# PreAmplifierBuffer.net
KiCad netlist of a schematic drawn in Altium Designer
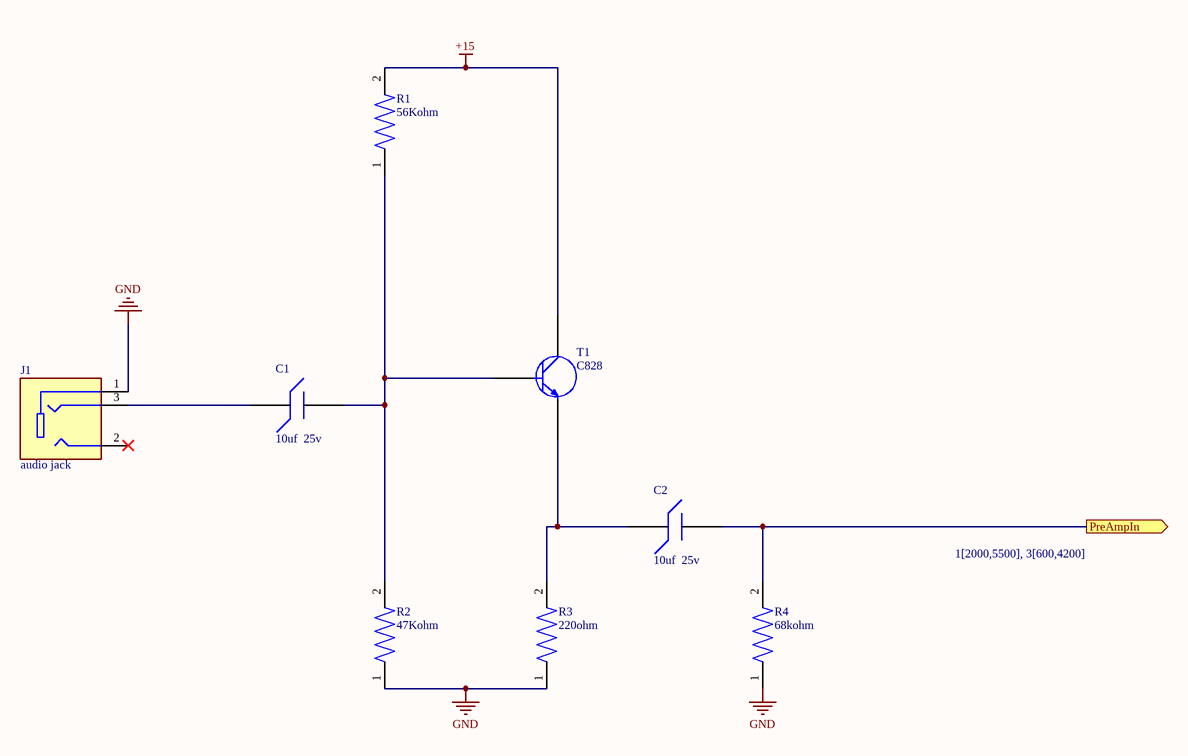
[diagram p0: PreAmplifierBuffer.SchDoc]

(export (version "E")
  (design (tool "Eeschema 10.0.6"))
  (components
    (comp (ref "C1")
      (value "10uf  25v")
      (footprint "Capasitor")
      (fields
        (field (name "MANUFACTURER") "Rubycon")
        (field (name "MANUFACTURER PART NUMBER") "25ZLG10MEFC4X7")
      )
      (libsource (lib "AudioAmplifierBasic") (part "25ZLG10MEFC4X7"))
    )
    (comp (ref "C2")
      (value "10uf  25v")
      (footprint "Capasitor")
      (fields
        (field (name "MANUFACTURER") "Rubycon")
        (field (name "MANUFACTURER PART NUMBER") "25ZLG10MEFC4X7")
      )
      (libsource (lib "AudioAmplifierBasic") (part "25ZLG10MEFC4X7"))
    )
    (comp (ref "J1")
      (value "audio jack")
      (footprint "AudiJack")
      (description "3 Pole(s), Solder Terminal, Jack")
      (fields (field (name "MANUFACTURER") "Same Sky") (field (name "MANUFACTURER PART NUMBER") "SJ1-3523N"))
      (libsource (lib "AudioAmplifierBasic") (part "SJ1-3523N"))
    )
    (comp (ref "R1")
      (value "56Kohm")
      (footprint "Resistor")
      (description "Fixed Resistor, Carbon Film, 0.125W, 56000ohm, 250V, 5% +/-Tol, -500,0ppm/Cel, Through Hole Mount")
      (fields
        (field (name "MANUFACTURER") "Stackpole Electronics")
        (field (name "MANUFACTURER PART NUMBER") "CF18JT56K0")
      )
      (libsource (lib "AudioAmplifierBasic") (part "CF18JT56K0"))
    )
    (comp (ref "R2")
      (value "47Kohm")
      (footprint "Resistor")
      (description "Fixed Resistor, Carbon Film, 0.5W, 47000ohm, 350V, 5% +/-Tol, -500,0ppm/Cel, Through Hole Mount")
      (fields
        (field (name "MANUFACTURER") "Stackpole Electronics")
        (field (name "MANUFACTURER PART NUMBER") "CF12JT47K0")
      )
      (libsource (lib "AudioAmplifierBasic") (part "CF12JT47K0"))
    )
    (comp (ref "R3")
      (value "220ohm")
      (footprint "Resistor")
      (description "RES SMD 220 OHM 1% 2W 4525")
      (fields (field (name "MANUFACTURER") "Riedon") (field (name "MANUFACTURER PART NUMBER") "S4-220RF1"))
      (libsource (lib "AudioAmplifierBasic") (part "S4-220RF1"))
    )
    (comp (ref "R4")
      (value "68kohm")
      (footprint "Resistor")
      (description "Fixed Resistor, Carbon Film, 0.25W, 68000ohm, 300V, 5% +/-Tol, -450,350ppm/Cel, Through Hole Mount")
      (fields
        (field (name "MANUFACTURER") "KOA Speer")
        (field (name "MANUFACTURER PART NUMBER") "CF1/4CT52R683J")
      )
      (libsource (lib "AudioAmplifierBasic") (part "CF1/4CT52R683J"))
    )
    (comp (ref "T1")
      (value "C828")
      (footprint "transistor")
      (description "Hall Effect Sensor, -65mT Min, 1-1.75V, Rectangular, Through Hole Mount")
      (fields
        (field (name "MANUFACTURER") "Honeywell Sensing & Control")
        (field (name "MANUFACTURER PART NUMBER") "SS49E-L")
      )
      (libsource (lib "AudioAmplifierBasic") (part "SS49E-L"))
    )
  )
  (nets
    (net (code "1") (name "+15") (class "Default")
      (node (ref "R1") (pin "2") (pinfunction "2_2") (pintype "passive"))
      (node (ref "T1") (pin "1") (pinfunction "13_1") (pintype "passive"))
    )
    (net (code "2") (name "/PreAmpIn") (class "Default")
      (node (ref "C2") (pin "1") (pinfunction "1_1") (pintype "passive"))
      (node (ref "R4") (pin "2") (pinfunction "2_2") (pintype "passive"))
    )
    (net (code "3") (name "GND") (class "Default")
      (node (ref "J1") (pin "1") (pinfunction "1_1") (pintype "passive"))
      (node (ref "R2") (pin "1") (pinfunction "1_1") (pintype "passive"))
      (node (ref "R3") (pin "1") (pinfunction "1_1") (pintype "passive"))
      (node (ref "R4") (pin "1") (pinfunction "1_1") (pintype "passive"))
    )
    (net (code "4") (name "Net-(C1-Pad1)") (class "Default")
      (node (ref "C1") (pin "1") (pinfunction "1_1") (pintype "passive"))
      (node (ref "R1") (pin "1") (pinfunction "1_1") (pintype "passive"))
      (node (ref "R2") (pin "2") (pinfunction "2_2") (pintype "passive"))
      (node (ref "T1") (pin "2") (pinfunction "2_2") (pintype "passive"))
    )
    (net (code "5") (name "Net-(C1-Pad2)") (class "Default")
      (node (ref "C1") (pin "2") (pinfunction "2_2") (pintype "passive"))
      (node (ref "J1") (pin "3") (pinfunction "3_3") (pintype "passive"))
    )
    (net (code "6") (name "Net-(T1-12)") (class "Default")
      (node (ref "C2") (pin "2") (pinfunction "2_2") (pintype "passive"))
      (node (ref "R3") (pin "2") (pinfunction "2_2") (pintype "passive"))
      (node (ref "T1") (pin "3") (pinfunction "12_3") (pintype "passive"))
    )
    (net (code "7") (name "unconnected-(J1-Pad2)") (class "Default")
      (node (ref "J1") (pin "2") (pinfunction "2_2") (pintype "passive+no_connect"))
    )
  )
)
